# T35_2_POWER_CONFIG.net
KiCad netlist of a schematic drawn in Altium Designer
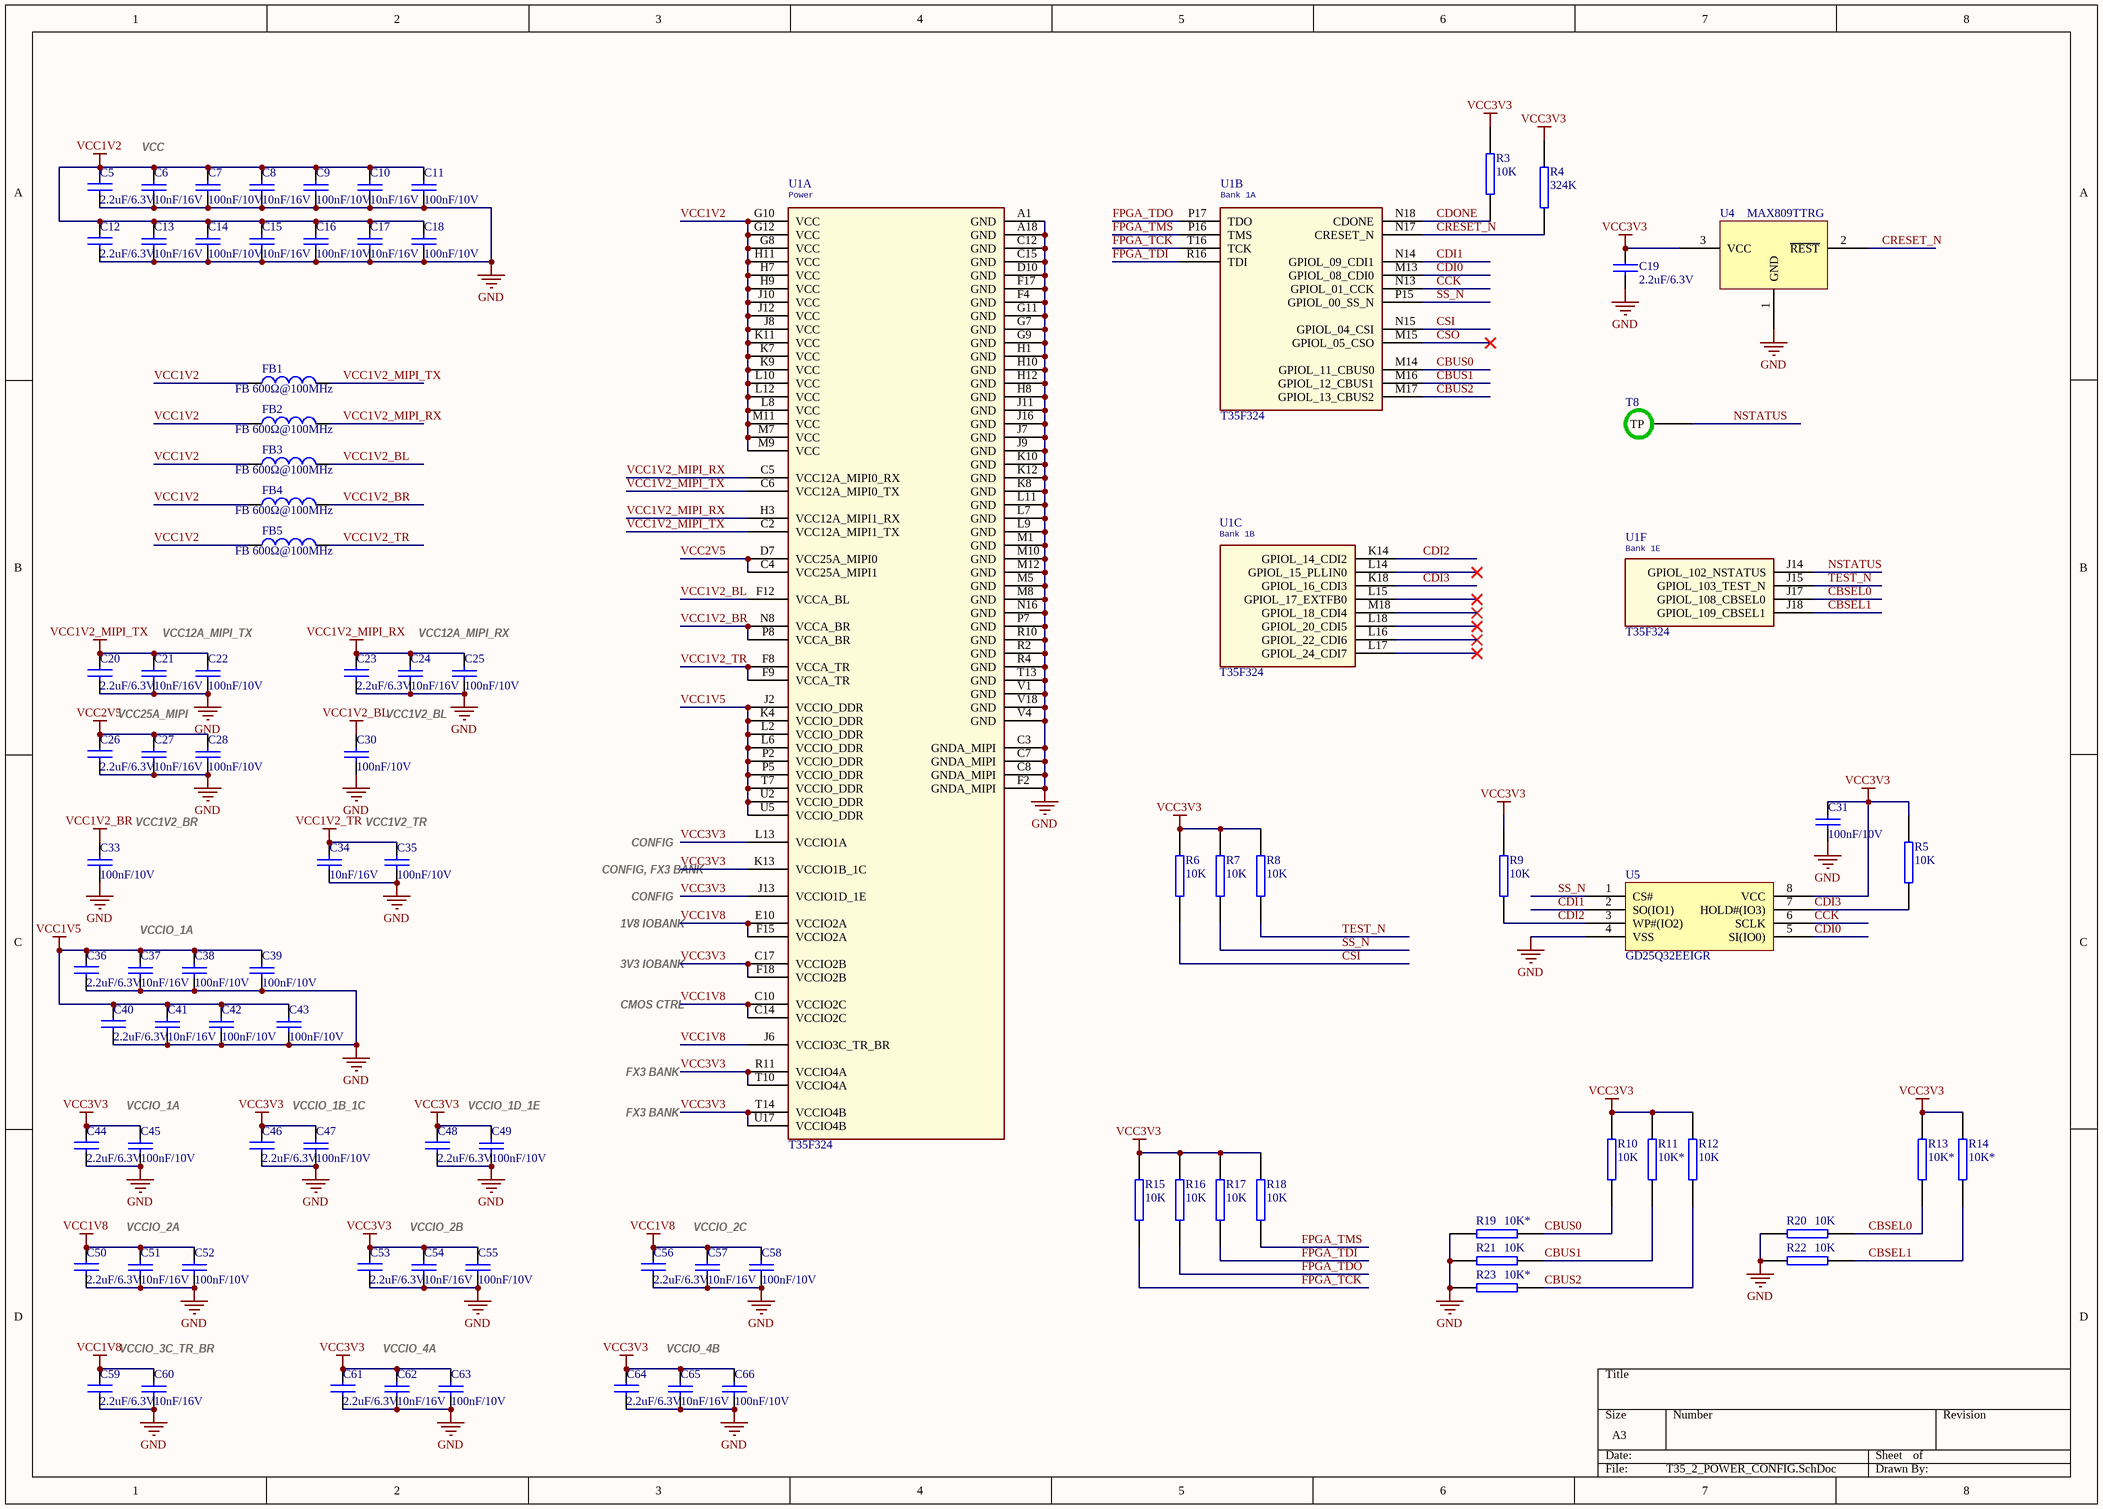
[diagram p0: T35_2_POWER_CONFIG.SchDoc]

(export (version "E")
  (design (tool "Eeschema 10.0.6"))
  (components
    (comp (ref "C5")
      (value "2.2uF/6.3V")
      (footprint "0201CS")
      (description "贴片电容")
      (libsource (lib "*") (part "CAPACITOR NON-POL"))
    )
    (comp (ref "C6")
      (value "10nF/16V")
      (footprint "0201CS")
      (description "贴片电容")
      (libsource (lib "*") (part "CAP"))
    )
    (comp (ref "C7")
      (value "100nF/10V")
      (footprint "0201CS")
      (description "贴片电容")
      (libsource (lib "*") (part "CAP"))
    )
    (comp (ref "C8")
      (value "10nF/16V")
      (footprint "0201CS")
      (description "贴片电容")
      (libsource (lib "*") (part "CAP"))
    )
    (comp (ref "C9")
      (value "100nF/10V")
      (footprint "0201CS")
      (description "贴片电容")
      (libsource (lib "*") (part "CAP"))
    )
    (comp (ref "C10")
      (value "10nF/16V")
      (footprint "0201CS")
      (description "贴片电容")
      (libsource (lib "*") (part "CAP"))
    )
    (comp (ref "C11")
      (value "100nF/10V")
      (footprint "0201CS")
      (description "贴片电容")
      (libsource (lib "*") (part "CAP"))
    )
    (comp (ref "C12")
      (value "2.2uF/6.3V")
      (footprint "0201CS")
      (description "贴片电容")
      (libsource (lib "*") (part "CAPACITOR NON-POL"))
    )
    (comp (ref "C13")
      (value "10nF/16V")
      (footprint "0201CS")
      (description "贴片电容")
      (libsource (lib "*") (part "CAP"))
    )
    (comp (ref "C14")
      (value "100nF/10V")
      (footprint "0201CS")
      (description "贴片电容")
      (libsource (lib "*") (part "CAP"))
    )
    (comp (ref "C15")
      (value "10nF/16V")
      (footprint "0201CS")
      (description "贴片电容")
      (libsource (lib "*") (part "CAP"))
    )
    (comp (ref "C16")
      (value "100nF/10V")
      (footprint "0201CS")
      (description "贴片电容")
      (libsource (lib "*") (part "CAP"))
    )
    (comp (ref "C17")
      (value "10nF/16V")
      (footprint "0201CS")
      (description "贴片电容")
      (libsource (lib "*") (part "CAP"))
    )
    (comp (ref "C18")
      (value "100nF/10V")
      (footprint "0201CS")
      (description "贴片电容")
      (libsource (lib "*") (part "CAP"))
    )
    (comp (ref "C19")
      (value "2.2uF/6.3V")
      (footprint "0201CS")
      (description "贴片电容")
      (libsource (lib "*") (part "CAPACITOR NON-POL"))
    )
    (comp (ref "C20")
      (value "2.2uF/6.3V")
      (footprint "0201CS")
      (description "贴片电容")
      (libsource (lib "*") (part "CAPACITOR NON-POL"))
    )
    (comp (ref "C21")
      (value "10nF/16V")
      (footprint "0201CS")
      (description "贴片电容")
      (libsource (lib "*") (part "CAP"))
    )
    (comp (ref "C22")
      (value "100nF/10V")
      (footprint "0201CS")
      (description "贴片电容")
      (libsource (lib "*") (part "CAP"))
    )
    (comp (ref "C23")
      (value "2.2uF/6.3V")
      (footprint "0201CS")
      (description "贴片电容")
      (libsource (lib "*") (part "CAPACITOR NON-POL"))
    )
    (comp (ref "C24")
      (value "10nF/16V")
      (footprint "0201CS")
      (description "贴片电容")
      (libsource (lib "*") (part "CAP"))
    )
    (comp (ref "C25")
      (value "100nF/10V")
      (footprint "0201CS")
      (description "贴片电容")
      (libsource (lib "*") (part "CAP"))
    )
    (comp (ref "C26")
      (value "2.2uF/6.3V")
      (footprint "0201CS")
      (description "贴片电容")
      (libsource (lib "*") (part "CAPACITOR NON-POL"))
    )
    (comp (ref "C27")
      (value "10nF/16V")
      (footprint "0201CS")
      (description "贴片电容")
      (libsource (lib "*") (part "CAP"))
    )
    (comp (ref "C28")
      (value "100nF/10V")
      (footprint "0201CS")
      (description "贴片电容")
      (libsource (lib "*") (part "CAP"))
    )
    (comp (ref "C30")
      (value "100nF/10V")
      (footprint "0201CS")
      (description "贴片电容")
      (libsource (lib "*") (part "CAP"))
    )
    (comp (ref "C31")
      (value "100nF/10V")
      (footprint "0201CS")
      (description "贴片电容")
      (libsource (lib "*") (part "CAP"))
    )
    (comp (ref "C33")
      (value "100nF/10V")
      (footprint "0201CS")
      (description "贴片电容")
      (libsource (lib "*") (part "CAP"))
    )
    (comp (ref "C34")
      (value "10nF/16V")
      (footprint "0201CS")
      (description "贴片电容")
      (libsource (lib "*") (part "CAP"))
    )
    (comp (ref "C35")
      (value "100nF/10V")
      (footprint "0201CS")
      (description "贴片电容")
      (libsource (lib "*") (part "CAP"))
    )
    (comp (ref "C36")
      (value "2.2uF/6.3V")
      (footprint "0201CS")
      (description "贴片电容")
      (libsource (lib "*") (part "CAPACITOR NON-POL"))
    )
    (comp (ref "C37")
      (value "10nF/16V")
      (footprint "0201CS")
      (description "贴片电容")
      (libsource (lib "*") (part "CAP"))
    )
    (comp (ref "C38")
      (value "100nF/10V")
      (footprint "0201CS")
      (description "贴片电容")
      (libsource (lib "*") (part "CAP"))
    )
    (comp (ref "C39")
      (value "100nF/10V")
      (footprint "0201CS")
      (description "贴片电容")
      (libsource (lib "*") (part "CAP"))
    )
    (comp (ref "C40")
      (value "2.2uF/6.3V")
      (footprint "0201CS")
      (description "贴片电容")
      (libsource (lib "*") (part "CAPACITOR NON-POL"))
    )
    (comp (ref "C41")
      (value "10nF/16V")
      (footprint "0201CS")
      (description "贴片电容")
      (libsource (lib "*") (part "CAP"))
    )
    (comp (ref "C42")
      (value "100nF/10V")
      (footprint "0201CS")
      (description "贴片电容")
      (libsource (lib "*") (part "CAP"))
    )
    (comp (ref "C43")
      (value "100nF/10V")
      (footprint "0201CS")
      (description "贴片电容")
      (libsource (lib "*") (part "CAP"))
    )
    (comp (ref "C44")
      (value "2.2uF/6.3V")
      (footprint "0201CS")
      (description "贴片电容")
      (libsource (lib "*") (part "CAPACITOR NON-POL"))
    )
    (comp (ref "C45")
      (value "100nF/10V")
      (footprint "0201CS")
      (description "贴片电容")
      (libsource (lib "*") (part "CAP"))
    )
    (comp (ref "C46")
      (value "2.2uF/6.3V")
      (footprint "0201CS")
      (description "贴片电容")
      (libsource (lib "*") (part "CAPACITOR NON-POL"))
    )
    (comp (ref "C47")
      (value "100nF/10V")
      (footprint "0201CS")
      (description "贴片电容")
      (libsource (lib "*") (part "CAP"))
    )
    (comp (ref "C48")
      (value "2.2uF/6.3V")
      (footprint "0201CS")
      (description "贴片电容")
      (libsource (lib "*") (part "CAPACITOR NON-POL"))
    )
    (comp (ref "C49")
      (value "100nF/10V")
      (footprint "0201CS")
      (description "贴片电容")
      (libsource (lib "*") (part "CAP"))
    )
    (comp (ref "C50")
      (value "2.2uF/6.3V")
      (footprint "0201CS")
      (description "贴片电容")
      (libsource (lib "*") (part "CAPACITOR NON-POL"))
    )
    (comp (ref "C51")
      (value "10nF/16V")
      (footprint "0201CS")
      (description "贴片电容")
      (libsource (lib "*") (part "CAP"))
    )
    (comp (ref "C52")
      (value "100nF/10V")
      (footprint "0201CS")
      (description "贴片电容")
      (libsource (lib "*") (part "CAP"))
    )
    (comp (ref "C53")
      (value "2.2uF/6.3V")
      (footprint "0201CS")
      (description "贴片电容")
      (libsource (lib "*") (part "CAPACITOR NON-POL"))
    )
    (comp (ref "C54")
      (value "10nF/16V")
      (footprint "0201CS")
      (description "贴片电容")
      (libsource (lib "*") (part "CAP"))
    )
    (comp (ref "C55")
      (value "100nF/10V")
      (footprint "0201CS")
      (description "贴片电容")
      (libsource (lib "*") (part "CAP"))
    )
    (comp (ref "C56")
      (value "2.2uF/6.3V")
      (footprint "0201CS")
      (description "贴片电容")
      (libsource (lib "*") (part "CAPACITOR NON-POL"))
    )
    (comp (ref "C57")
      (value "10nF/16V")
      (footprint "0201CS")
      (description "贴片电容")
      (libsource (lib "*") (part "CAP"))
    )
    (comp (ref "C58")
      (value "100nF/10V")
      (footprint "0201CS")
      (description "贴片电容")
      (libsource (lib "*") (part "CAP"))
    )
    (comp (ref "C59")
      (value "2.2uF/6.3V")
      (footprint "0201CS")
      (description "贴片电容")
      (libsource (lib "*") (part "CAPACITOR NON-POL"))
    )
    (comp (ref "C60")
      (value "10nF/16V")
      (footprint "0201CS")
      (description "贴片电容")
      (libsource (lib "*") (part "CAP"))
    )
    (comp (ref "C61")
      (value "2.2uF/6.3V")
      (footprint "0201CS")
      (description "贴片电容")
      (libsource (lib "*") (part "CAPACITOR NON-POL"))
    )
    (comp (ref "C62")
      (value "10nF/16V")
      (footprint "0201CS")
      (description "贴片电容")
      (libsource (lib "*") (part "CAP"))
    )
    (comp (ref "C63")
      (value "100nF/10V")
      (footprint "0201CS")
      (description "贴片电容")
      (libsource (lib "*") (part "CAP"))
    )
    (comp (ref "C64")
      (value "2.2uF/6.3V")
      (footprint "0201CS")
      (description "贴片电容")
      (libsource (lib "*") (part "CAPACITOR NON-POL"))
    )
    (comp (ref "C65")
      (value "10nF/16V")
      (footprint "0201CS")
      (description "贴片电容")
      (libsource (lib "*") (part "CAP"))
    )
    (comp (ref "C66")
      (value "100nF/10V")
      (footprint "0201CS")
      (description "贴片电容")
      (libsource (lib "*") (part "CAP"))
    )
    (comp (ref "FB1")
      (value "FB 600Ω@100MHz")
      (footprint "FB0603")
      (description "贴片磁珠")
      (libsource (lib "Miscellaneous Devices") (part "Inductor"))
    )
    (comp (ref "FB2")
      (value "FB 600Ω@100MHz")
      (footprint "FB0603")
      (description "贴片磁珠")
      (libsource (lib "Miscellaneous Devices") (part "Inductor"))
    )
    (comp (ref "FB3")
      (value "FB 600Ω@100MHz")
      (footprint "FB0603")
      (description "贴片磁珠")
      (libsource (lib "Miscellaneous Devices") (part "Inductor"))
    )
    (comp (ref "FB4")
      (value "FB 600Ω@100MHz")
      (footprint "FB0603")
      (description "贴片磁珠")
      (libsource (lib "Miscellaneous Devices") (part "Inductor"))
    )
    (comp (ref "FB5")
      (value "FB 600Ω@100MHz")
      (footprint "FB0603")
      (description "贴片磁珠")
      (libsource (lib "Miscellaneous Devices") (part "Inductor"))
    )
    (comp (ref "R3")
      (value "10K")
      (footprint "0201RS")
      (description "贴片电阻")
      (libsource (lib "*") (part "RES2"))
    )
    (comp (ref "R4")
      (value "324K")
      (footprint "0402RS")
      (description "贴片电阻")
      (libsource (lib "*") (part "RES2"))
    )
    (comp (ref "R5")
      (value "10K")
      (footprint "0201RS")
      (description "贴片电阻")
      (libsource (lib "*") (part "RES2"))
    )
    (comp (ref "R6")
      (value "10K")
      (footprint "0201RS")
      (description "贴片电阻")
      (libsource (lib "*") (part "RES2"))
    )
    (comp (ref "R7")
      (value "10K")
      (footprint "0201RS")
      (description "贴片电阻")
      (libsource (lib "*") (part "RES2"))
    )
    (comp (ref "R8")
      (value "10K")
      (footprint "0201RS")
      (description "贴片电阻")
      (libsource (lib "*") (part "RES2"))
    )
    (comp (ref "R9")
      (value "10K")
      (footprint "0201RS")
      (description "贴片电阻")
      (libsource (lib "*") (part "RES2"))
    )
    (comp (ref "R10")
      (value "10K")
      (footprint "0201RS")
      (description "贴片电阻")
      (libsource (lib "*") (part "RES2"))
    )
    (comp (ref "R11")
      (value "10K*")
      (footprint "0201RS")
      (description "贴片电阻")
      (libsource (lib "*") (part "RES2"))
    )
    (comp (ref "R12")
      (value "10K")
      (footprint "0201RS")
      (description "贴片电阻")
      (libsource (lib "*") (part "RES2"))
    )
    (comp (ref "R13")
      (value "10K*")
      (footprint "0201RS")
      (description "贴片电阻")
      (libsource (lib "*") (part "RES2"))
    )
    (comp (ref "R14")
      (value "10K*")
      (footprint "0201RS")
      (description "贴片电阻")
      (libsource (lib "*") (part "RES2"))
    )
    (comp (ref "R15")
      (value "10K")
      (footprint "0201RS")
      (description "贴片电阻")
      (libsource (lib "*") (part "RES2"))
    )
    (comp (ref "R16")
      (value "10K")
      (footprint "0201RS")
      (description "贴片电阻")
      (libsource (lib "*") (part "RES2"))
    )
    (comp (ref "R17")
      (value "10K")
      (footprint "0201RS")
      (description "贴片电阻")
      (libsource (lib "*") (part "RES2"))
    )
    (comp (ref "R18")
      (value "10K")
      (footprint "0201RS")
      (description "贴片电阻")
      (libsource (lib "*") (part "RES2"))
    )
    (comp (ref "R19")
      (value "10K*")
      (footprint "0201RS")
      (description "贴片电阻")
      (libsource (lib "*") (part "RES2"))
    )
    (comp (ref "R20")
      (value "10K")
      (footprint "0201RS")
      (description "贴片电阻")
      (libsource (lib "*") (part "RES2"))
    )
    (comp (ref "R21")
      (value "10K")
      (footprint "0201RS")
      (description "贴片电阻")
      (libsource (lib "*") (part "RES2"))
    )
    (comp (ref "R22")
      (value "10K")
      (footprint "0201RS")
      (description "贴片电阻")
      (libsource (lib "*") (part "RES2"))
    )
    (comp (ref "R23")
      (value "10K*")
      (footprint "0201RS")
      (description "贴片电阻")
      (libsource (lib "*") (part "RES2"))
    )
    (comp (ref "T8")
      (value "~")
      (footprint "TP-S")
      (description "测试点")
      (libsource (lib "QHY_SCHLIB") (part "TP"))
    )
    (comp (ref "U1")
      (value "T35F324")
      (footprint "T35-F324-BGA100P9X9-81A")
      (description "FPGA芯片")
      (libsource (lib "orcadt35-v1.0_Library") (part "T35F324"))
    )
    (comp (ref "U4")
      (value "MAX809TTRG")
      (footprint "MAX809")
      (description "复位芯片")
      (libsource (lib "QHY_SCHLIB") (part "MAX809"))
    )
    (comp (ref "U5")
      (value "GD25Q32EEIGR")
      (footprint "SON127P600-8N-USON8")
      (description "SPI Flash")
      (libsource (lib "LEC") (part "GD25Q64ESIG"))
    )
  )
  (nets
    (net (code "1") (name "/CBSEL0") (class "Default")
      (node (ref "R13") (pin "2") (pinfunction "2_2") (pintype "passive"))
      (node (ref "R20") (pin "2") (pinfunction "2_2") (pintype "passive"))
      (node (ref "U1") (pin "J17") (pinfunction "GPIOL_108_CBSEL0_J17") (pintype "passive"))
    )
    (net (code "2") (name "/CBSEL1") (class "Default")
      (node (ref "R14") (pin "2") (pinfunction "2_2") (pintype "passive"))
      (node (ref "R22") (pin "2") (pinfunction "2_2") (pintype "passive"))
      (node (ref "U1") (pin "J18") (pinfunction "GPIOL_109_CBSEL1_J18") (pintype "passive"))
    )
    (net (code "3") (name "/CBUS0") (class "Default")
      (node (ref "R10") (pin "2") (pinfunction "2_2") (pintype "passive"))
      (node (ref "R19") (pin "2") (pinfunction "2_2") (pintype "passive"))
      (node (ref "U1") (pin "M14") (pinfunction "GPIOL_11_CBUS0_M14") (pintype "passive"))
    )
    (net (code "4") (name "/CBUS1") (class "Default")
      (node (ref "R11") (pin "2") (pinfunction "2_2") (pintype "passive"))
      (node (ref "R21") (pin "2") (pinfunction "2_2") (pintype "passive"))
      (node (ref "U1") (pin "M16") (pinfunction "GPIOL_12_CBUS1_M16") (pintype "passive"))
    )
    (net (code "5") (name "/CBUS2") (class "Default")
      (node (ref "R12") (pin "2") (pinfunction "2_2") (pintype "passive"))
      (node (ref "R23") (pin "2") (pinfunction "2_2") (pintype "passive"))
      (node (ref "U1") (pin "M17") (pinfunction "GPIOL_13_CBUS2_M17") (pintype "passive"))
    )
    (net (code "6") (name "/CCK") (class "Default")
      (node (ref "U1") (pin "N13") (pinfunction "GPIOL_01_CCK_N13") (pintype "passive"))
      (node (ref "U5") (pin "6") (pinfunction "SCLK_6") (pintype "passive"))
    )
    (net (code "7") (name "/CDI0") (class "Default")
      (node (ref "U1") (pin "M13") (pinfunction "GPIOL_08_CDI0_M13") (pintype "passive"))
      (node (ref "U5") (pin "5") (pinfunction "SI(IO0)_5") (pintype "passive"))
    )
    (net (code "8") (name "/CDI1") (class "Default")
      (node (ref "U1") (pin "N14") (pinfunction "GPIOL_09_CDI1_N14") (pintype "passive"))
      (node (ref "U5") (pin "2") (pinfunction "SO(IO1)_2") (pintype "passive"))
    )
    (net (code "9") (name "/CDI2") (class "Default")
      (node (ref "R9") (pin "1") (pinfunction "1_1") (pintype "passive"))
      (node (ref "U1") (pin "K14") (pinfunction "GPIOL_14_CDI2_K14") (pintype "passive"))
      (node (ref "U5") (pin "3") (pinfunction "WP#(IO2)_3") (pintype "passive"))
    )
    (net (code "10") (name "/CDI3") (class "Default")
      (node (ref "R5") (pin "1") (pinfunction "1_1") (pintype "passive"))
      (node (ref "U1") (pin "K18") (pinfunction "GPIOL_16_CDI3_K18") (pintype "passive"))
      (node (ref "U5") (pin "7") (pinfunction "HOLD#(IO3)_7") (pintype "passive"))
    )
    (net (code "11") (name "/CDONE") (class "Default")
      (node (ref "R3") (pin "2") (pinfunction "2_2") (pintype "passive"))
      (node (ref "U1") (pin "N18") (pinfunction "CDONE_N18") (pintype "passive"))
    )
    (net (code "12") (name "/CRESET_N") (class "Default")
      (node (ref "R4") (pin "2") (pinfunction "2_2") (pintype "passive"))
      (node (ref "U1") (pin "N17") (pinfunction "CRESET_N_N17") (pintype "passive"))
      (node (ref "U4") (pin "2") (pinfunction "~{REST}_2") (pintype "passive"))
    )
    (net (code "13") (name "/CSI") (class "Default")
      (node (ref "R6") (pin "2") (pinfunction "2_2") (pintype "passive"))
      (node (ref "U1") (pin "N15") (pinfunction "GPIOL_04_CSI_N15") (pintype "passive"))
    )
    (net (code "14") (name "/CSO") (class "Default")
      (node (ref "U1") (pin "M15") (pinfunction "GPIOL_05_CSO_M15") (pintype "passive+no_connect"))
    )
    (net (code "15") (name "/FPGA_TCK") (class "Default")
      (node (ref "R15") (pin "2") (pinfunction "2_2") (pintype "passive"))
      (node (ref "U1") (pin "T16") (pinfunction "TCK_T16") (pintype "passive"))
    )
    (net (code "16") (name "/FPGA_TDI") (class "Default")
      (node (ref "R17") (pin "2") (pinfunction "2_2") (pintype "passive"))
      (node (ref "U1") (pin "R16") (pinfunction "TDI_R16") (pintype "passive"))
    )
    (net (code "17") (name "/FPGA_TDO") (class "Default")
      (node (ref "R16") (pin "2") (pinfunction "2_2") (pintype "passive"))
      (node (ref "U1") (pin "P17") (pinfunction "TDO_P17") (pintype "passive"))
    )
    (net (code "18") (name "/FPGA_TMS") (class "Default")
      (node (ref "R18") (pin "2") (pinfunction "2_2") (pintype "passive"))
      (node (ref "U1") (pin "P16") (pinfunction "TMS_P16") (pintype "passive"))
    )
    (net (code "19") (name "/NSTATUS") (class "Default")
      (node (ref "T8") (pin "1") (pinfunction "TP_1") (pintype "passive"))
      (node (ref "U1") (pin "J14") (pinfunction "GPIOL_102_NSTATUS_J14") (pintype "passive"))
    )
    (net (code "20") (name "/SS_N") (class "Default")
      (node (ref "R7") (pin "2") (pinfunction "2_2") (pintype "passive"))
      (node (ref "U1") (pin "P15") (pinfunction "GPIOL_00_SS_N_P15") (pintype "passive"))
      (node (ref "U5") (pin "1") (pinfunction "CS#_1") (pintype "passive"))
    )
    (net (code "21") (name "/TEST_N") (class "Default")
      (node (ref "R8") (pin "2") (pinfunction "2_2") (pintype "passive"))
      (node (ref "U1") (pin "J15") (pinfunction "GPIOL_103_TEST_N_J15") (pintype "passive"))
    )
    (net (code "22") (name "GND") (class "Default")
      (node (ref "C10") (pin "2") (pinfunction "2_2") (pintype "passive"))
      (node (ref "C11") (pin "2") (pinfunction "2_2") (pintype "passive"))
      (node (ref "C12") (pin "2") (pinfunction "2_2") (pintype "passive"))
      (node (ref "C13") (pin "2") (pinfunction "2_2") (pintype "passive"))
      (node (ref "C14") (pin "2") (pinfunction "2_2") (pintype "passive"))
      (node (ref "C15") (pin "2") (pinfunction "2_2") (pintype "passive"))
      (node (ref "C16") (pin "2") (pinfunction "2_2") (pintype "passive"))
      (node (ref "C17") (pin "2") (pinfunction "2_2") (pintype "passive"))
      (node (ref "C18") (pin "2") (pinfunction "2_2") (pintype "passive"))
      (node (ref "C19") (pin "2") (pinfunction "2_2") (pintype "passive"))
      (node (ref "C20") (pin "2") (pinfunction "2_2") (pintype "passive"))
      (node (ref "C21") (pin "2") (pinfunction "2_2") (pintype "passive"))
      (node (ref "C22") (pin "2") (pinfunction "2_2") (pintype "passive"))
      (node (ref "C23") (pin "2") (pinfunction "2_2") (pintype "passive"))
      (node (ref "C24") (pin "2") (pinfunction "2_2") (pintype "passive"))
      (node (ref "C25") (pin "2") (pinfunction "2_2") (pintype "passive"))
      (node (ref "C26") (pin "2") (pinfunction "2_2") (pintype "passive"))
      (node (ref "C27") (pin "2") (pinfunction "2_2") (pintype "passive"))
      (node (ref "C28") (pin "2") (pinfunction "2_2") (pintype "passive"))
      (node (ref "C30") (pin "2") (pinfunction "2_2") (pintype "passive"))
      (node (ref "C31") (pin "2") (pinfunction "2_2") (pintype "passive"))
      (node (ref "C33") (pin "2") (pinfunction "2_2") (pintype "passive"))
      (node (ref "C34") (pin "2") (pinfunction "2_2") (pintype "passive"))
      (node (ref "C35") (pin "2") (pinfunction "2_2") (pintype "passive"))
      (node (ref "C36") (pin "2") (pinfunction "2_2") (pintype "passive"))
      (node (ref "C37") (pin "2") (pinfunction "2_2") (pintype "passive"))
      (node (ref "C38") (pin "2") (pinfunction "2_2") (pintype "passive"))
      (node (ref "C39") (pin "2") (pinfunction "2_2") (pintype "passive"))
      (node (ref "C40") (pin "2") (pinfunction "2_2") (pintype "passive"))
      (node (ref "C41") (pin "2") (pinfunction "2_2") (pintype "passive"))
      (node (ref "C42") (pin "2") (pinfunction "2_2") (pintype "passive"))
      (node (ref "C43") (pin "2") (pinfunction "2_2") (pintype "passive"))
      (node (ref "C44") (pin "2") (pinfunction "2_2") (pintype "passive"))
      (node (ref "C45") (pin "2") (pinfunction "2_2") (pintype "passive"))
      (node (ref "C46") (pin "2") (pinfunction "2_2") (pintype "passive"))
      (node (ref "C47") (pin "2") (pinfunction "2_2") (pintype "passive"))
      (node (ref "C48") (pin "2") (pinfunction "2_2") (pintype "passive"))
      (node (ref "C49") (pin "2") (pinfunction "2_2") (pintype "passive"))
      (node (ref "C5") (pin "2") (pinfunction "2_2") (pintype "passive"))
      (node (ref "C50") (pin "2") (pinfunction "2_2") (pintype "passive"))
      (node (ref "C51") (pin "2") (pinfunction "2_2") (pintype "passive"))
      (node (ref "C52") (pin "2") (pinfunction "2_2") (pintype "passive"))
      (node (ref "C53") (pin "2") (pinfunction "2_2") (pintype "passive"))
      (node (ref "C54") (pin "2") (pinfunction "2_2") (pintype "passive"))
      (node (ref "C55") (pin "2") (pinfunction "2_2") (pintype "passive"))
      (node (ref "C56") (pin "2") (pinfunction "2_2") (pintype "passive"))
      (node (ref "C57") (pin "2") (pinfunction "2_2") (pintype "passive"))
      (node (ref "C58") (pin "2") (pinfunction "2_2") (pintype "passive"))
      (node (ref "C59") (pin "2") (pinfunction "2_2") (pintype "passive"))
      (node (ref "C6") (pin "2") (pinfunction "2_2") (pintype "passive"))
      (node (ref "C60") (pin "2") (pinfunction "2_2") (pintype "passive"))
      (node (ref "C61") (pin "2") (pinfunction "2_2") (pintype "passive"))
      (node (ref "C62") (pin "2") (pinfunction "2_2") (pintype "passive"))
      (node (ref "C63") (pin "2") (pinfunction "2_2") (pintype "passive"))
      (node (ref "C64") (pin "2") (pinfunction "2_2") (pintype "passive"))
      (node (ref "C65") (pin "2") (pinfunction "2_2") (pintype "passive"))
      (node (ref "C66") (pin "2") (pinfunction "2_2") (pintype "passive"))
      (node (ref "C7") (pin "2") (pinfunction "2_2") (pintype "passive"))
      (node (ref "C8") (pin "2") (pinfunction "2_2") (pintype "passive"))
      (node (ref "C9") (pin "2") (pinfunction "2_2") (pintype "passive"))
      (node (ref "R19") (pin "1") (pinfunction "1_1") (pintype "passive"))
      (node (ref "R20") (pin "1") (pinfunction "1_1") (pintype "passive"))
      (node (ref "R21") (pin "1") (pinfunction "1_1") (pintype "passive"))
      (node (ref "R22") (pin "1") (pinfunction "1_1") (pintype "passive"))
      (node (ref "R23") (pin "1") (pinfunction "1_1") (pintype "passive"))
      (node (ref "U1") (pin "A1") (pinfunction "GND_A1") (pintype "passive"))
      (node (ref "U1") (pin "A18") (pinfunction "GND_A18") (pintype "passive"))
      (node (ref "U1") (pin "C12") (pinfunction "GND_C12") (pintype "passive"))
      (node (ref "U1") (pin "C15") (pinfunction "GND_C15") (pintype "passive"))
      (node (ref "U1") (pin "C3") (pinfunction "GNDA_MIPI_C3") (pintype "passive"))
      (node (ref "U1") (pin "C7") (pinfunction "GNDA_MIPI_C7") (pintype "passive"))
      (node (ref "U1") (pin "C8") (pinfunction "GNDA_MIPI_C8") (pintype "passive"))
      (node (ref "U1") (pin "D10") (pinfunction "GND_D10") (pintype "passive"))
      (node (ref "U1") (pin "F17") (pinfunction "GND_F17") (pintype "passive"))
      (node (ref "U1") (pin "F2") (pinfunction "GNDA_MIPI_F2") (pintype "passive"))
      (node (ref "U1") (pin "F4") (pinfunction "GND_F4") (pintype "passive"))
      (node (ref "U1") (pin "G11") (pinfunction "GND_G11") (pintype "passive"))
      (node (ref "U1") (pin "G7") (pinfunction "GND_G7") (pintype "passive"))
      (node (ref "U1") (pin "G9") (pinfunction "GND_G9") (pintype "passive"))
      (node (ref "U1") (pin "H1") (pinfunction "GND_H1") (pintype "passive"))
      (node (ref "U1") (pin "H10") (pinfunction "GND_H10") (pintype "passive"))
      (node (ref "U1") (pin "H12") (pinfunction "GND_H12") (pintype "passive"))
      (node (ref "U1") (pin "H8") (pinfunction "GND_H8") (pintype "passive"))
      (node (ref "U1") (pin "J11") (pinfunction "GND_J11") (pintype "passive"))
      (node (ref "U1") (pin "J16") (pinfunction "GND_J16") (pintype "passive"))
      (node (ref "U1") (pin "J7") (pinfunction "GND_J7") (pintype "passive"))
      (node (ref "U1") (pin "J9") (pinfunction "GND_J9") (pintype "passive"))
      (node (ref "U1") (pin "K10") (pinfunction "GND_K10") (pintype "passive"))
      (node (ref "U1") (pin "K12") (pinfunction "GND_K12") (pintype "passive"))
      (node (ref "U1") (pin "K8") (pinfunction "GND_K8") (pintype "passive"))
      (node (ref "U1") (pin "L11") (pinfunction "GND_L11") (pintype "passive"))
      (node (ref "U1") (pin "L7") (pinfunction "GND_L7") (pintype "passive"))
      (node (ref "U1") (pin "L9") (pinfunction "GND_L9") (pintype "passive"))
      (node (ref "U1") (pin "M1") (pinfunction "GND_M1") (pintype "passive"))
      (node (ref "U1") (pin "M10") (pinfunction "GND_M10") (pintype "passive"))
      (node (ref "U1") (pin "M12") (pinfunction "GND_M12") (pintype "passive"))
      (node (ref "U1") (pin "M5") (pinfunction "GND_M5") (pintype "passive"))
      (node (ref "U1") (pin "M8") (pinfunction "GND_M8") (pintype "passive"))
      (node (ref "U1") (pin "N16") (pinfunction "GND_N16") (pintype "passive"))
      (node (ref "U1") (pin "P7") (pinfunction "GND_P7") (pintype "passive"))
      (node (ref "U1") (pin "R10") (pinfunction "GND_R10") (pintype "passive"))
      (node (ref "U1") (pin "R2") (pinfunction "GND_R2") (pintype "passive"))
      (node (ref "U1") (pin "R4") (pinfunction "GND_R4") (pintype "passive"))
      (node (ref "U1") (pin "T13") (pinfunction "GND_T13") (pintype "passive"))
      (node (ref "U1") (pin "V1") (pinfunction "GND_V1") (pintype "passive"))
      (node (ref "U1") (pin "V18") (pinfunction "GND_V18") (pintype "passive"))
      (node (ref "U1") (pin "V4") (pinfunction "GND_V4") (pintype "passive"))
      (node (ref "U4") (pin "1") (pinfunction "GND_1") (pintype "passive"))
      (node (ref "U5") (pin "4") (pinfunction "VSS_4") (pintype "passive"))
    )
    (net (code "23") (name "VCC1V2") (class "Default")
      (node (ref "C10") (pin "1") (pinfunction "1_1") (pintype "passive"))
      (node (ref "C11") (pin "1") (pinfunction "1_1") (pintype "passive"))
      (node (ref "C12") (pin "1") (pinfunction "1_1") (pintype "passive"))
      (node (ref "C13") (pin "1") (pinfunction "1_1") (pintype "passive"))
      (node (ref "C14") (pin "1") (pinfunction "1_1") (pintype "passive"))
      (node (ref "C15") (pin "1") (pinfunction "1_1") (pintype "passive"))
      (node (ref "C16") (pin "1") (pinfunction "1_1") (pintype "passive"))
      (node (ref "C17") (pin "1") (pinfunction "1_1") (pintype "passive"))
      (node (ref "C18") (pin "1") (pinfunction "1_1") (pintype "passive"))
      (node (ref "C5") (pin "1") (pinfunction "1_1") (pintype "passive"))
      (node (ref "C6") (pin "1") (pinfunction "1_1") (pintype "passive"))
      (node (ref "C7") (pin "1") (pinfunction "1_1") (pintype "passive"))
      (node (ref "C8") (pin "1") (pinfunction "1_1") (pintype "passive"))
      (node (ref "C9") (pin "1") (pinfunction "1_1") (pintype "passive"))
      (node (ref "FB1") (pin "1") (pinfunction "1_1") (pintype "passive"))
      (node (ref "FB2") (pin "1") (pinfunction "1_1") (pintype "passive"))
      (node (ref "FB3") (pin "1") (pinfunction "1_1") (pintype "passive"))
      (node (ref "FB4") (pin "1") (pinfunction "1_1") (pintype "passive"))
      (node (ref "FB5") (pin "1") (pinfunction "1_1") (pintype "passive"))
      (node (ref "U1") (pin "G10") (pinfunction "VCC_G10") (pintype "passive"))
      (node (ref "U1") (pin "G12") (pinfunction "VCC_G12") (pintype "passive"))
      (node (ref "U1") (pin "G8") (pinfunction "VCC_G8") (pintype "passive"))
      (node (ref "U1") (pin "H11") (pinfunction "VCC_H11") (pintype "passive"))
      (node (ref "U1") (pin "H7") (pinfunction "VCC_H7") (pintype "passive"))
      (node (ref "U1") (pin "H9") (pinfunction "VCC_H9") (pintype "passive"))
      (node (ref "U1") (pin "J10") (pinfunction "VCC_J10") (pintype "passive"))
      (node (ref "U1") (pin "J12") (pinfunction "VCC_J12") (pintype "passive"))
      (node (ref "U1") (pin "J8") (pinfunction "VCC_J8") (pintype "passive"))
      (node (ref "U1") (pin "K11") (pinfunction "VCC_K11") (pintype "passive"))
      (node (ref "U1") (pin "K7") (pinfunction "VCC_K7") (pintype "passive"))
      (node (ref "U1") (pin "K9") (pinfunction "VCC_K9") (pintype "passive"))
      (node (ref "U1") (pin "L10") (pinfunction "VCC_L10") (pintype "passive"))
      (node (ref "U1") (pin "L12") (pinfunction "VCC_L12") (pintype "passive"))
      (node (ref "U1") (pin "L8") (pinfunction "VCC_L8") (pintype "passive"))
      (node (ref "U1") (pin "M11") (pinfunction "VCC_M11") (pintype "passive"))
      (node (ref "U1") (pin "M7") (pinfunction "VCC_M7") (pintype "passive"))
      (node (ref "U1") (pin "M9") (pinfunction "VCC_M9") (pintype "passive"))
    )
    (net (code "24") (name "VCC1V2_BL") (class "Default")
      (node (ref "C30") (pin "1") (pinfunction "1_1") (pintype "passive"))
      (node (ref "FB3") (pin "2") (pinfunction "2_2") (pintype "passive"))
      (node (ref "U1") (pin "F12") (pinfunction "VCCA_BL_F12") (pintype "passive"))
    )
    (net (code "25") (name "VCC1V2_BR") (class "Default")
      (node (ref "C33") (pin "1") (pinfunction "1_1") (pintype "passive"))
      (node (ref "FB4") (pin "2") (pinfunction "2_2") (pintype "passive"))
      (node (ref "U1") (pin "N8") (pinfunction "VCCA_BR_N8") (pintype "passive"))
      (node (ref "U1") (pin "P8") (pinfunction "VCCA_BR_P8") (pintype "passive"))
    )
    (net (code "26") (name "VCC1V2_MIPI_RX") (class "Default")
      (node (ref "C23") (pin "1") (pinfunction "1_1") (pintype "passive"))
      (node (ref "C24") (pin "1") (pinfunction "1_1") (pintype "passive"))
      (node (ref "C25") (pin "1") (pinfunction "1_1") (pintype "passive"))
      (node (ref "FB2") (pin "2") (pinfunction "2_2") (pintype "passive"))
      (node (ref "U1") (pin "C5") (pinfunction "VCC12A_MIPI0_RX_C5") (pintype "passive"))
      (node (ref "U1") (pin "H3") (pinfunction "VCC12A_MIPI1_RX_H3") (pintype "passive"))
    )
    (net (code "27") (name "VCC1V2_MIPI_TX") (class "Default")
      (node (ref "C20") (pin "1") (pinfunction "1_1") (pintype "passive"))
      (node (ref "C21") (pin "1") (pinfunction "1_1") (pintype "passive"))
      (node (ref "C22") (pin "1") (pinfunction "1_1") (pintype "passive"))
      (node (ref "FB1") (pin "2") (pinfunction "2_2") (pintype "passive"))
      (node (ref "U1") (pin "C2") (pinfunction "VCC12A_MIPI1_TX_C2") (pintype "passive"))
      (node (ref "U1") (pin "C6") (pinfunction "VCC12A_MIPI0_TX_C6") (pintype "passive"))
    )
    (net (code "28") (name "VCC1V2_TR") (class "Default")
      (node (ref "C34") (pin "1") (pinfunction "1_1") (pintype "passive"))
      (node (ref "C35") (pin "1") (pinfunction "1_1") (pintype "passive"))
      (node (ref "FB5") (pin "2") (pinfunction "2_2") (pintype "passive"))
      (node (ref "U1") (pin "F8") (pinfunction "VCCA_TR_F8") (pintype "passive"))
      (node (ref "U1") (pin "F9") (pinfunction "VCCA_TR_F9") (pintype "passive"))
    )
    (net (code "29") (name "VCC1V5") (class "Default")
      (node (ref "C36") (pin "1") (pinfunction "1_1") (pintype "passive"))
      (node (ref "C37") (pin "1") (pinfunction "1_1") (pintype "passive"))
      (node (ref "C38") (pin "1") (pinfunction "1_1") (pintype "passive"))
      (node (ref "C39") (pin "1") (pinfunction "1_1") (pintype "passive"))
      (node (ref "C40") (pin "1") (pinfunction "1_1") (pintype "passive"))
      (node (ref "C41") (pin "1") (pinfunction "1_1") (pintype "passive"))
      (node (ref "C42") (pin "1") (pinfunction "1_1") (pintype "passive"))
      (node (ref "C43") (pin "1") (pinfunction "1_1") (pintype "passive"))
      (node (ref "U1") (pin "J2") (pinfunction "VCCIO_DDR_J2") (pintype "passive"))
      (node (ref "U1") (pin "K4") (pinfunction "VCCIO_DDR_K4") (pintype "passive"))
      (node (ref "U1") (pin "L2") (pinfunction "VCCIO_DDR_L2") (pintype "passive"))
      (node (ref "U1") (pin "L6") (pinfunction "VCCIO_DDR_L6") (pintype "passive"))
      (node (ref "U1") (pin "P2") (pinfunction "VCCIO_DDR_P2") (pintype "passive"))
      (node (ref "U1") (pin "P5") (pinfunction "VCCIO_DDR_P5") (pintype "passive"))
      (node (ref "U1") (pin "T7") (pinfunction "VCCIO_DDR_T7") (pintype "passive"))
      (node (ref "U1") (pin "U2") (pinfunction "VCCIO_DDR_U2") (pintype "passive"))
      (node (ref "U1") (pin "U5") (pinfunction "VCCIO_DDR_U5") (pintype "passive"))
    )
    (net (code "30") (name "VCC1V8") (class "Default")
      (node (ref "C50") (pin "1") (pinfunction "1_1") (pintype "passive"))
      (node (ref "C51") (pin "1") (pinfunction "1_1") (pintype "passive"))
      (node (ref "C52") (pin "1") (pinfunction "1_1") (pintype "passive"))
      (node (ref "C56") (pin "1") (pinfunction "1_1") (pintype "passive"))
      (node (ref "C57") (pin "1") (pinfunction "1_1") (pintype "passive"))
      (node (ref "C58") (pin "1") (pinfunction "1_1") (pintype "passive"))
      (node (ref "C59") (pin "1") (pinfunction "1_1") (pintype "passive"))
      (node (ref "C60") (pin "1") (pinfunction "1_1") (pintype "passive"))
      (node (ref "U1") (pin "C10") (pinfunction "VCCIO2C_C10") (pintype "passive"))
      (node (ref "U1") (pin "C14") (pinfunction "VCCIO2C_C14") (pintype "passive"))
      (node (ref "U1") (pin "E10") (pinfunction "VCCIO2A_E10") (pintype "passive"))
      (node (ref "U1") (pin "F15") (pinfunction "VCCIO2A_F15") (pintype "passive"))
      (node (ref "U1") (pin "J6") (pinfunction "VCCIO3C_TR_BR_J6") (pintype "passive"))
    )
    (net (code "31") (name "VCC2V5") (class "Default")
      (node (ref "C26") (pin "1") (pinfunction "1_1") (pintype "passive"))
      (node (ref "C27") (pin "1") (pinfunction "1_1") (pintype "passive"))
      (node (ref "C28") (pin "1") (pinfunction "1_1") (pintype "passive"))
      (node (ref "U1") (pin "C4") (pinfunction "VCC25A_MIPI1_C4") (pintype "passive"))
      (node (ref "U1") (pin "D7") (pinfunction "VCC25A_MIPI0_D7") (pintype "passive"))
    )
    (net (code "32") (name "VCC3V3") (class "Default")
      (node (ref "C19") (pin "1") (pinfunction "1_1") (pintype "passive"))
      (node (ref "C31") (pin "1") (pinfunction "1_1") (pintype "passive"))
      (node (ref "C44") (pin "1") (pinfunction "1_1") (pintype "passive"))
      (node (ref "C45") (pin "1") (pinfunction "1_1") (pintype "passive"))
      (node (ref "C46") (pin "1") (pinfunction "1_1") (pintype "passive"))
      (node (ref "C47") (pin "1") (pinfunction "1_1") (pintype "passive"))
      (node (ref "C48") (pin "1") (pinfunction "1_1") (pintype "passive"))
      (node (ref "C49") (pin "1") (pinfunction "1_1") (pintype "passive"))
      (node (ref "C53") (pin "1") (pinfunction "1_1") (pintype "passive"))
      (node (ref "C54") (pin "1") (pinfunction "1_1") (pintype "passive"))
      (node (ref "C55") (pin "1") (pinfunction "1_1") (pintype "passive"))
      (node (ref "C61") (pin "1") (pinfunction "1_1") (pintype "passive"))
      (node (ref "C62") (pin "1") (pinfunction "1_1") (pintype "passive"))
      (node (ref "C63") (pin "1") (pinfunction "1_1") (pintype "passive"))
      (node (ref "C64") (pin "1") (pinfunction "1_1") (pintype "passive"))
      (node (ref "C65") (pin "1") (pinfunction "1_1") (pintype "passive"))
      (node (ref "C66") (pin "1") (pinfunction "1_1") (pintype "passive"))
      (node (ref "R10") (pin "1") (pinfunction "1_1") (pintype "passive"))
      (node (ref "R11") (pin "1") (pinfunction "1_1") (pintype "passive"))
      (node (ref "R12") (pin "1") (pinfunction "1_1") (pintype "passive"))
      (node (ref "R13") (pin "1") (pinfunction "1_1") (pintype "passive"))
      (node (ref "R14") (pin "1") (pinfunction "1_1") (pintype "passive"))
      (node (ref "R15") (pin "1") (pinfunction "1_1") (pintype "passive"))
      (node (ref "R16") (pin "1") (pinfunction "1_1") (pintype "passive"))
      (node (ref "R17") (pin "1") (pinfunction "1_1") (pintype "passive"))
      (node (ref "R18") (pin "1") (pinfunction "1_1") (pintype "passive"))
      (node (ref "R3") (pin "1") (pinfunction "1_1") (pintype "passive"))
      (node (ref "R4") (pin "1") (pinfunction "1_1") (pintype "passive"))
      (node (ref "R5") (pin "2") (pinfunction "2_2") (pintype "passive"))
      (node (ref "R6") (pin "1") (pinfunction "1_1") (pintype "passive"))
      (node (ref "R7") (pin "1") (pinfunction "1_1") (pintype "passive"))
      (node (ref "R8") (pin "1") (pinfunction "1_1") (pintype "passive"))
      (node (ref "R9") (pin "2") (pinfunction "2_2") (pintype "passive"))
      (node (ref "U1") (pin "C17") (pinfunction "VCCIO2B_C17") (pintype "passive"))
      (node (ref "U1") (pin "F18") (pinfunction "VCCIO2B_F18") (pintype "passive"))
      (node (ref "U1") (pin "J13") (pinfunction "VCCIO1D_1E_J13") (pintype "passive"))
      (node (ref "U1") (pin "K13") (pinfunction "VCCIO1B_1C_K13") (pintype "passive"))
      (node (ref "U1") (pin "L13") (pinfunction "VCCIO1A_L13") (pintype "passive"))
      (node (ref "U1") (pin "R11") (pinfunction "VCCIO4A_R11") (pintype "passive"))
      (node (ref "U1") (pin "T10") (pinfunction "VCCIO4A_T10") (pintype "passive"))
      (node (ref "U1") (pin "T14") (pinfunction "VCCIO4B_T14") (pintype "passive"))
      (node (ref "U1") (pin "U17") (pinfunction "VCCIO4B_U17") (pintype "passive"))
      (node (ref "U4") (pin "3") (pinfunction "VCC_3") (pintype "passive"))
      (node (ref "U5") (pin "8") (pinfunction "VCC_8") (pintype "passive"))
    )
    (net (code "33") (name "unconnected-(U1C-GPIOL_15_PLLIN0-PadL14)") (class "Default")
      (node (ref "U1") (pin "L14") (pinfunction "GPIOL_15_PLLIN0_L14") (pintype "passive+no_connect"))
    )
    (net (code "34") (name "unconnected-(U1C-GPIOL_17_EXTFB0-PadL15)") (class "Default")
      (node (ref "U1") (pin "L15") (pinfunction "GPIOL_17_EXTFB0_L15") (pintype "passive+no_connect"))
    )
    (net (code "35") (name "unconnected-(U1C-GPIOL_18_CDI4-PadM18)") (class "Default")
      (node (ref "U1") (pin "M18") (pinfunction "GPIOL_18_CDI4_M18") (pintype "passive+no_connect"))
    )
    (net (code "36") (name "unconnected-(U1C-GPIOL_20_CDI5-PadL18)") (class "Default")
      (node (ref "U1") (pin "L18") (pinfunction "GPIOL_20_CDI5_L18") (pintype "passive+no_connect"))
    )
    (net (code "37") (name "unconnected-(U1C-GPIOL_22_CDI6-PadL16)") (class "Default")
      (node (ref "U1") (pin "L16") (pinfunction "GPIOL_22_CDI6_L16") (pintype "passive+no_connect"))
    )
    (net (code "38") (name "unconnected-(U1C-GPIOL_24_CDI7-PadL17)") (class "Default")
      (node (ref "U1") (pin "L17") (pinfunction "GPIOL_24_CDI7_L17") (pintype "passive+no_connect"))
    )
  )
)
